# Relay_Interface.net
KiCad netlist of a schematic drawn in Altium Designer
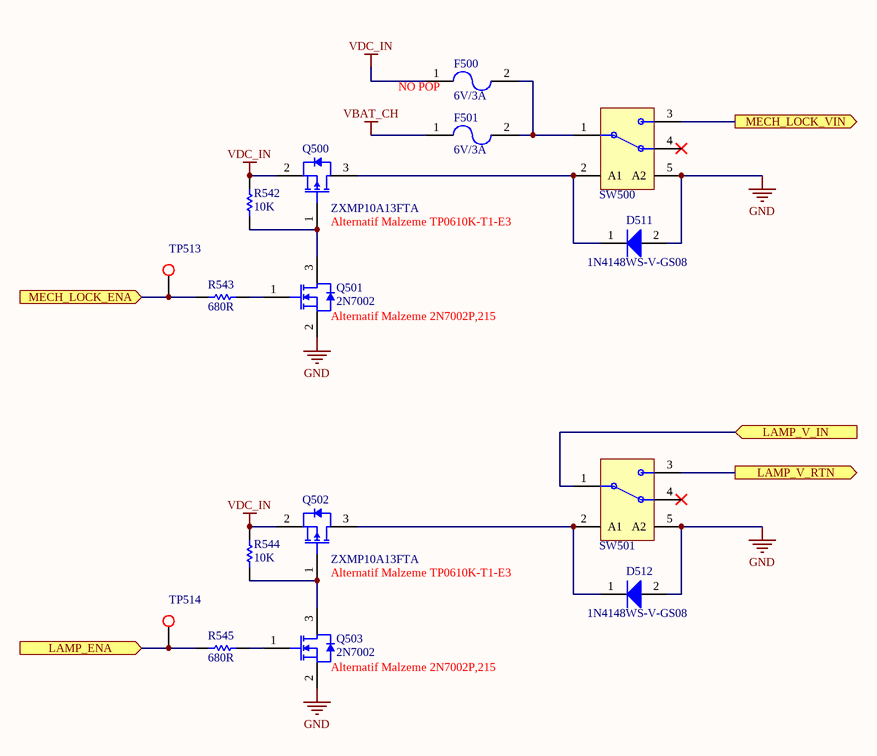
[diagram p0: Relay_Interface.SchDoc]

(export (version "E")
  (design (tool "Eeschema 10.0.6"))
  (components
    (comp (ref "D511")
      (value "1N4148WS-V-GS08")
      (footprint "SOD65P270X115-2N")
      (description "Diode, Switching, 1.2V @100mA, 75V, SOD-323")
      (fields (field (name "MANUFACTURER") "VISHAY"))
      (libsource (lib "Anime_Semiconductor") (part "AS1D-815M-SI10-0000"))
    )
    (comp (ref "D512")
      (value "1N4148WS-V-GS08")
      (footprint "SOD65P270X115-2N")
      (description "Diode, Switching, 1.2V @100mA, 75V, SOD-323")
      (fields (field (name "MANUFACTURER") "VISHAY"))
      (libsource (lib "Anime_Semiconductor") (part "AS1D-815M-SI10-0000"))
    )
    (comp (ref "F500")
      (value "6V/3A")
      (footprint "AE12-000L-S000-9300")
      (description "Resettable Fuse, 6V, 3A, SMD, 1812")
      (fields
        (field (name "MANUFACTURER") "TE Connectivity")
        (field (name "MANUFACTURER PART NUMBER") "miniSMDC300F")
        (field (name "ASSEMBLY") "NO POP")
      )
      (libsource (lib "Anime_Electromechanical") (part "AE12-000L-S000-9300"))
    )
    (comp (ref "F501")
      (value "6V/3A")
      (footprint "AE12-000L-S000-9300")
      (description "Resettable Fuse, 6V, 3A, SMD, 1812")
      (fields
        (field (name "MANUFACTURER") "TE Connectivity")
        (field (name "MANUFACTURER PART NUMBER") "miniSMDC300F")
      )
      (libsource (lib "Anime_Electromechanical") (part "AE12-000L-S000-9300"))
    )
    (comp (ref "Q500")
      (value "ZXMP10A13FTA")
      (footprint "SOT95P230X110-3N")
      (description "Transistor, MOSFET, P, 100V, -0.7A, 1R @-10V, ZXMP10A13FTA, SOT23")
      (fields (field (name "MANUFACTURER") "Diodes"))
      (libsource (lib "Anime_Semiconductor") (part "AS27-870H-SI20-0000"))
    )
    (comp (ref "Q501")
      (value "2N7002")
      (footprint "SOT90P247X115-3N")
      (description "Transistor, MOSFET, N, 60V, 115mA, 2N7002, SOT23")
      (fields (field (name "MANUFACTURER") "Fairchild"))
      (libsource (lib "Anime_Semiconductor") (part "AS26-810M-SI20-0000"))
    )
    (comp (ref "Q502")
      (value "ZXMP10A13FTA")
      (footprint "SOT95P230X110-3N")
      (description "Transistor, MOSFET, P, 100V, -0.7A, 1R @-10V, ZXMP10A13FTA, SOT23")
      (fields (field (name "MANUFACTURER") "Diodes"))
      (libsource (lib "Anime_Semiconductor") (part "AS27-870H-SI20-0000"))
    )
    (comp (ref "Q503")
      (value "2N7002")
      (footprint "SOT90P247X115-3N")
      (description "Transistor, MOSFET, N, 60V, 115mA, 2N7002, SOT23")
      (fields (field (name "MANUFACTURER") "Fairchild"))
      (libsource (lib "Anime_Semiconductor") (part "AS26-810M-SI20-0000"))
    )
    (comp (ref "R542")
      (value "10K")
      (footprint "RESC2012X07N")
      (description "RES, E24, Thick Film, SMD, 10K, 1%, 0.125W, 0805")
      (fields
        (field (name "MANUFACTURER") "Panasonic")
        (field (name "MANUFACTURER PART NUMBER") "ERJ-6ENF1002V")
      )
      (libsource (lib "Anime_Resistor") (part "AR19-4100-S4B2-0000"))
    )
    (comp (ref "R543")
      (value "680R")
      (footprint "RESC1005X04N")
      (description "RES, E24, Thick Film, SMD, 680R, 1%, 0.1W, 0402")
      (fields
        (field (name "MANUFACTURER") "Panasonic")
        (field (name "MANUFACTURER PART NUMBER") "ERJ-2RKF6800X")
      )
      (libsource (lib "Anime_Resistor") (part "AR19-2680-S2B2-0000"))
    )
    (comp (ref "R544")
      (value "10K")
      (footprint "RESC2012X07N")
      (description "RES, E24, Thick Film, SMD, 10K, 1%, 0.125W, 0805")
      (fields
        (field (name "MANUFACTURER") "Panasonic")
        (field (name "MANUFACTURER PART NUMBER") "ERJ-6ENF1002V")
      )
      (libsource (lib "Anime_Resistor") (part "AR19-4100-S4B2-0000"))
    )
    (comp (ref "R545")
      (value "680R")
      (footprint "RESC1005X04N")
      (description "RES, E24, Thick Film, SMD, 680R, 1%, 0.1W, 0402")
      (fields
        (field (name "MANUFACTURER") "Panasonic")
        (field (name "MANUFACTURER PART NUMBER") "ERJ-2RKF6800X")
      )
      (libsource (lib "Anime_Resistor") (part "AR19-2680-S2B2-0000"))
    )
    (comp (ref "SW500")
      (value "Relay")
      (footprint "AE11-0100-T000-0100")
      (description "Relay, Single Form A, 24VDC, 10A, TH")
      (fields (field (name "MANUFACTURER") "Omron") (field (name "MANUFACTURER PART NUMBER") "G5LE-1A4 DC24"))
      (libsource (lib "Anime_Electromechanical") (part "AE11-0100-T000-0100"))
    )
    (comp (ref "SW501")
      (value "Relay")
      (footprint "AE11-0100-T000-0100")
      (description "Relay, Single Form A, 24VDC, 10A, TH")
      (fields (field (name "MANUFACTURER") "Omron") (field (name "MANUFACTURER PART NUMBER") "G5LE-1A4 DC24"))
      (libsource (lib "Anime_Electromechanical") (part "AE11-0100-T000-0100"))
    )
    (comp (ref "TP513")
      (value "AEMT-C00S-1000-0000")
      (footprint "TP100")
      (description "Test Point, Circular, 1mm")
      (libsource (lib "Anime_Electromechanical") (part "AEMT-C00S-1000-0000"))
    )
    (comp (ref "TP514")
      (value "AEMT-C00S-1000-0000")
      (footprint "TP100")
      (description "Test Point, Circular, 1mm")
      (libsource (lib "Anime_Electromechanical") (part "AEMT-C00S-1000-0000"))
    )
  )
  (nets
    (net (code "1") (name "/LAMP_ENA") (class "Default")
      (node (ref "R545") (pin "2") (pinfunction "2_2") (pintype "passive"))
      (node (ref "TP514") (pin "1") (pintype "passive"))
    )
    (net (code "2") (name "/LAMP_V_IN") (class "Default")
      (node (ref "SW501") (pin "1") (pinfunction "1_1") (pintype "passive"))
    )
    (net (code "3") (name "/LAMP_V_RTN") (class "Default")
      (node (ref "SW501") (pin "3") (pinfunction "3_3") (pintype "passive"))
    )
    (net (code "4") (name "/MECH_LOCK_ENA") (class "Default")
      (node (ref "R543") (pin "2") (pinfunction "2_2") (pintype "passive"))
      (node (ref "TP513") (pin "1") (pintype "passive"))
    )
    (net (code "5") (name "/MECH_LOCK_VIN") (class "Default")
      (node (ref "SW500") (pin "3") (pinfunction "3_3") (pintype "passive"))
    )
    (net (code "6") (name "GND") (class "Default")
      (node (ref "D511") (pin "2") (pinfunction "A_2") (pintype "passive"))
      (node (ref "D512") (pin "2") (pinfunction "A_2") (pintype "passive"))
      (node (ref "Q501") (pin "2") (pinfunction "Source_2") (pintype "passive"))
      (node (ref "Q503") (pin "2") (pinfunction "Source_2") (pintype "passive"))
      (node (ref "SW500") (pin "5") (pinfunction "A2_5") (pintype "power_in"))
      (node (ref "SW501") (pin "5") (pinfunction "A2_5") (pintype "power_in"))
    )
    (net (code "7") (name "Net-(D511-K)") (class "Default")
      (node (ref "D511") (pin "1") (pinfunction "K_1") (pintype "passive"))
      (node (ref "Q500") (pin "3") (pinfunction "Drain_3") (pintype "passive"))
      (node (ref "SW500") (pin "2") (pinfunction "A1_2") (pintype "power_in"))
    )
    (net (code "8") (name "Net-(D512-K)") (class "Default")
      (node (ref "D512") (pin "1") (pinfunction "K_1") (pintype "passive"))
      (node (ref "Q502") (pin "3") (pinfunction "Drain_3") (pintype "passive"))
      (node (ref "SW501") (pin "2") (pinfunction "A1_2") (pintype "power_in"))
    )
    (net (code "9") (name "Net-(F500-Pad2)") (class "Default")
      (node (ref "F500") (pin "2") (pinfunction "2_2") (pintype "passive"))
      (node (ref "F501") (pin "2") (pinfunction "2_2") (pintype "passive"))
      (node (ref "SW500") (pin "1") (pinfunction "1_1") (pintype "passive"))
    )
    (net (code "10") (name "Net-(Q500-Gate)") (class "Default")
      (node (ref "Q500") (pin "1") (pinfunction "Gate_1") (pintype "passive"))
      (node (ref "Q501") (pin "3") (pinfunction "Drain_3") (pintype "passive"))
      (node (ref "R542") (pin "2") (pinfunction "2_2") (pintype "passive"))
    )
    (net (code "11") (name "Net-(Q501-Gate)") (class "Default")
      (node (ref "Q501") (pin "1") (pinfunction "Gate_1") (pintype "passive"))
      (node (ref "R543") (pin "1") (pinfunction "1_1") (pintype "passive"))
    )
    (net (code "12") (name "Net-(Q502-Gate)") (class "Default")
      (node (ref "Q502") (pin "1") (pinfunction "Gate_1") (pintype "passive"))
      (node (ref "Q503") (pin "3") (pinfunction "Drain_3") (pintype "passive"))
      (node (ref "R544") (pin "2") (pinfunction "2_2") (pintype "passive"))
    )
    (net (code "13") (name "Net-(Q503-Gate)") (class "Default")
      (node (ref "Q503") (pin "1") (pinfunction "Gate_1") (pintype "passive"))
      (node (ref "R545") (pin "1") (pinfunction "1_1") (pintype "passive"))
    )
    (net (code "14") (name "VBAT_CH") (class "Default")
      (node (ref "F501") (pin "1") (pinfunction "1_1") (pintype "passive"))
    )
    (net (code "15") (name "VDC_IN") (class "Default")
      (node (ref "F500") (pin "1") (pinfunction "1_1") (pintype "passive"))
      (node (ref "Q500") (pin "2") (pinfunction "Source_2") (pintype "passive"))
      (node (ref "Q502") (pin "2") (pinfunction "Source_2") (pintype "passive"))
      (node (ref "R542") (pin "1") (pinfunction "1_1") (pintype "passive"))
      (node (ref "R544") (pin "1") (pinfunction "1_1") (pintype "passive"))
    )
    (net (code "16") (name "unconnected-(SW500-Pad4)") (class "Default")
      (node (ref "SW500") (pin "4") (pinfunction "4_4") (pintype "passive+no_connect"))
    )
    (net (code "17") (name "unconnected-(SW501-Pad4)") (class "Default")
      (node (ref "SW501") (pin "4") (pinfunction "4_4") (pintype "passive+no_connect"))
    )
  )
)
